# PCM1794.net
KiCad netlist of a schematic drawn in EAGLE
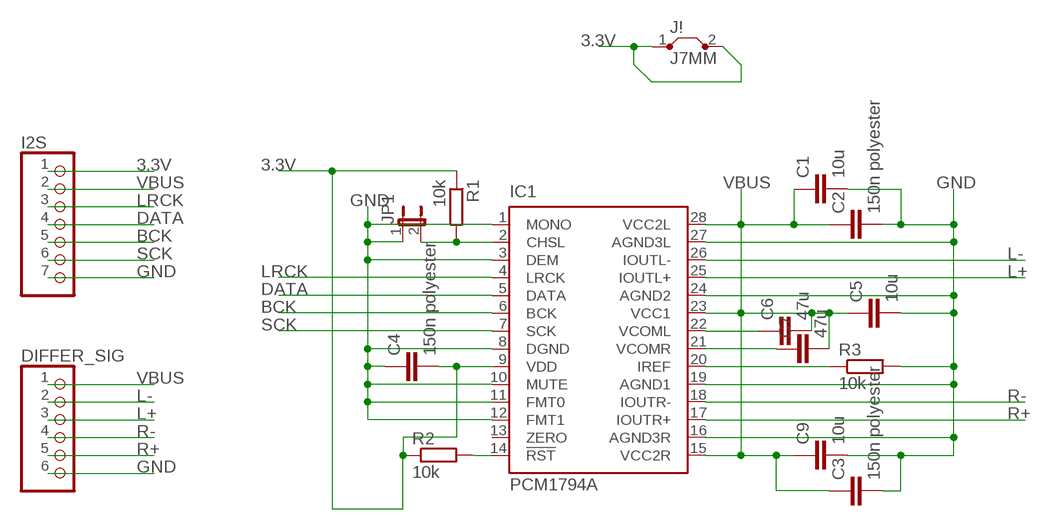
[diagram p0: schematic, sheet 1]

(export (version "E")
  (design (tool "Eeschema 10.0.6"))
  (components
    (comp (ref "C1")
      (value "10u")
      (footprint "eagle-import:C025-050X050")
      (libsource (lib "eagle-import") (part "C-EU025-050X050"))
    )
    (comp (ref "C2")
      (value "150n polyester")
      (footprint "eagle-import:C7.5B4")
      (libsource (lib "eagle-import") (part "C7.5/4"))
    )
    (comp (ref "C3")
      (value "150n polyester")
      (footprint "eagle-import:C7.5B4")
      (libsource (lib "eagle-import") (part "C7.5/4"))
    )
    (comp (ref "C4")
      (value "150n polyester")
      (footprint "eagle-import:C7.5B4")
      (libsource (lib "eagle-import") (part "C7.5/4"))
    )
    (comp (ref "C5")
      (value "10u")
      (footprint "eagle-import:C025-050X050")
      (libsource (lib "eagle-import") (part "C-EU025-050X050"))
    )
    (comp (ref "C6")
      (value "47u")
      (footprint "eagle-import:C025-050X050")
      (libsource (lib "eagle-import") (part "C-EU025-050X050"))
    )
    (comp (ref "C7")
      (value "47u")
      (footprint "eagle-import:C025-050X050")
      (libsource (lib "eagle-import") (part "C-EU025-050X050"))
    )
    (comp (ref "C9")
      (value "10u")
      (footprint "eagle-import:C025-050X050")
      (libsource (lib "eagle-import") (part "C-EU025-050X050"))
    )
    (comp (ref "DIFFER_SIG")
      (value "PINHD-1X6/90")
      (footprint "eagle-import:1X06_90")
      (libsource (lib "eagle-import") (part "PINHD-1X6/90"))
    )
    (comp (ref "I2S")
      (value "PINHD-1X7")
      (footprint "eagle-import:1X07")
      (libsource (lib "eagle-import") (part "PINHD-1X7"))
    )
    (comp (ref "IC1")
      (value "PCM1794A")
      (footprint "eagle-import:DB_R-PDSO-G28")
      (fields (field (name "MF") "TEXAS INSTRUMENTS") (field (name "MPN") "PCM1792DB"))
      (libsource (lib "eagle-import") (part "PCM1794A"))
    )
    (comp (ref "J!")
      (value "J7MM")
      (footprint "eagle-import:07")
      (libsource (lib "eagle-import") (part "J7MM"))
    )
    (comp (ref "JP1")
      (value "JP1E")
      (footprint "eagle-import:JP1")
      (libsource (lib "eagle-import") (part "JP1E"))
    )
    (comp (ref "R1")
      (value "10k")
      (footprint "eagle-import:0207_7")
      (libsource (lib "eagle-import") (part "R-EU_0207/7"))
    )
    (comp (ref "R2")
      (value "10k")
      (footprint "eagle-import:0207_7")
      (libsource (lib "eagle-import") (part "R-EU_0207/7"))
    )
    (comp (ref "R3")
      (value "10k")
      (footprint "eagle-import:0207_7")
      (libsource (lib "eagle-import") (part "R-EU_0207/7"))
    )
  )
  (nets
    (net (code "1") (name "/3.3V") (class "Default")
      (node (ref "C4") (pin "2") (pinfunction "2_2") (pintype "passive"))
      (node (ref "I2S") (pin "1") (pinfunction "1_1") (pintype "passive"))
      (node (ref "IC1") (pin "9") (pinfunction "VDD_9") (pintype "input"))
      (node (ref "J!") (pin "1") (pinfunction "1_1") (pintype "passive"))
      (node (ref "J!") (pin "2") (pinfunction "2_2") (pintype "passive"))
      (node (ref "R1") (pin "1") (pinfunction "1_1") (pintype "passive"))
      (node (ref "R2") (pin "1") (pinfunction "1_1") (pintype "passive"))
    )
    (net (code "2") (name "/BCK") (class "Default")
      (node (ref "I2S") (pin "5") (pinfunction "5_5") (pintype "passive"))
      (node (ref "IC1") (pin "6") (pinfunction "BCK_6") (pintype "input"))
    )
    (net (code "3") (name "/DATA") (class "Default")
      (node (ref "I2S") (pin "4") (pinfunction "4_4") (pintype "passive"))
      (node (ref "IC1") (pin "5") (pinfunction "DATA_5") (pintype "input"))
    )
    (net (code "4") (name "/GND") (class "Default")
      (node (ref "C1") (pin "2") (pinfunction "2_2") (pintype "passive"))
      (node (ref "C2") (pin "2") (pinfunction "2_2") (pintype "passive"))
      (node (ref "C3") (pin "2") (pinfunction "2_2") (pintype "passive"))
      (node (ref "C4") (pin "1") (pinfunction "1_1") (pintype "passive"))
      (node (ref "C5") (pin "2") (pinfunction "2_2") (pintype "passive"))
      (node (ref "C9") (pin "2") (pinfunction "2_2") (pintype "passive"))
      (node (ref "DIFFER_SIG") (pin "6") (pinfunction "6_6") (pintype "passive"))
      (node (ref "I2S") (pin "7") (pinfunction "7_7") (pintype "passive"))
      (node (ref "IC1") (pin "1") (pinfunction "MONO_1") (pintype "bidirectional"))
      (node (ref "IC1") (pin "10") (pinfunction "MUTE_10") (pintype "bidirectional"))
      (node (ref "IC1") (pin "11") (pinfunction "FMT0_11") (pintype "input"))
      (node (ref "IC1") (pin "12") (pinfunction "FMT1_12") (pintype "input"))
      (node (ref "IC1") (pin "16") (pinfunction "AGND3R_16") (pintype "input"))
      (node (ref "IC1") (pin "19") (pinfunction "AGND1_19") (pintype "input"))
      (node (ref "IC1") (pin "24") (pinfunction "AGND2_24") (pintype "input"))
      (node (ref "IC1") (pin "27") (pinfunction "AGND3L_27") (pintype "input"))
      (node (ref "IC1") (pin "3") (pinfunction "DEM_3") (pintype "input"))
      (node (ref "IC1") (pin "8") (pinfunction "DGND_8") (pintype "input"))
      (node (ref "JP1") (pin "1") (pinfunction "1_1") (pintype "passive"))
      (node (ref "R3") (pin "2") (pinfunction "2_2") (pintype "passive"))
    )
    (net (code "5") (name "/L+") (class "Default")
      (node (ref "DIFFER_SIG") (pin "3") (pinfunction "3_3") (pintype "passive"))
      (node (ref "IC1") (pin "25") (pinfunction "IOUTL+_25") (pintype "output"))
    )
    (net (code "6") (name "/L-") (class "Default")
      (node (ref "DIFFER_SIG") (pin "2") (pinfunction "2_2") (pintype "passive"))
      (node (ref "IC1") (pin "26") (pinfunction "IOUTL-_26") (pintype "output"))
    )
    (net (code "7") (name "/LRCK") (class "Default")
      (node (ref "I2S") (pin "3") (pinfunction "3_3") (pintype "passive"))
      (node (ref "IC1") (pin "4") (pinfunction "LRCK_4") (pintype "input"))
    )
    (net (code "8") (name "/R+") (class "Default")
      (node (ref "DIFFER_SIG") (pin "5") (pinfunction "5_5") (pintype "passive"))
      (node (ref "IC1") (pin "17") (pinfunction "IOUTR+_17") (pintype "output"))
    )
    (net (code "9") (name "/R-") (class "Default")
      (node (ref "DIFFER_SIG") (pin "4") (pinfunction "4_4") (pintype "passive"))
      (node (ref "IC1") (pin "18") (pinfunction "IOUTR-_18") (pintype "output"))
    )
    (net (code "10") (name "/SCK") (class "Default")
      (node (ref "I2S") (pin "6") (pinfunction "6_6") (pintype "passive"))
      (node (ref "IC1") (pin "7") (pinfunction "SCK_7") (pintype "input"))
    )
    (net (code "11") (name "/VBUS") (class "Default")
      (node (ref "C1") (pin "1") (pinfunction "1_1") (pintype "passive"))
      (node (ref "C2") (pin "1") (pinfunction "1_1") (pintype "passive"))
      (node (ref "C3") (pin "1") (pinfunction "1_1") (pintype "passive"))
      (node (ref "C5") (pin "1") (pinfunction "1_1") (pintype "passive"))
      (node (ref "C6") (pin "2") (pinfunction "2_2") (pintype "passive"))
      (node (ref "C7") (pin "2") (pinfunction "2_2") (pintype "passive"))
      (node (ref "C9") (pin "1") (pinfunction "1_1") (pintype "passive"))
      (node (ref "DIFFER_SIG") (pin "1") (pinfunction "1_1") (pintype "passive"))
      (node (ref "I2S") (pin "2") (pinfunction "2_2") (pintype "passive"))
      (node (ref "IC1") (pin "15") (pinfunction "VCC2R_15") (pintype "input"))
      (node (ref "IC1") (pin "23") (pinfunction "VCC1_23") (pintype "input"))
      (node (ref "IC1") (pin "28") (pinfunction "VCC2L_28") (pintype "input"))
    )
    (net (code "12") (name "Net-(IC1-CHSL)") (class "Default")
      (node (ref "IC1") (pin "2") (pinfunction "CHSL_2") (pintype "bidirectional"))
      (node (ref "JP1") (pin "2") (pinfunction "2_2") (pintype "passive"))
      (node (ref "R1") (pin "2") (pinfunction "2_2") (pintype "passive"))
    )
    (net (code "13") (name "Net-(IC1-IREF)") (class "Default")
      (node (ref "IC1") (pin "20") (pinfunction "IREF_20") (pintype "output"))
      (node (ref "R3") (pin "1") (pinfunction "1_1") (pintype "passive"))
    )
    (net (code "14") (name "Net-(IC1-VCOML)") (class "Default")
      (node (ref "C6") (pin "1") (pinfunction "1_1") (pintype "passive"))
      (node (ref "IC1") (pin "22") (pinfunction "VCOML_22") (pintype "input"))
    )
    (net (code "15") (name "Net-(IC1-VCOMR)") (class "Default")
      (node (ref "C7") (pin "1") (pinfunction "1_1") (pintype "passive"))
      (node (ref "IC1") (pin "21") (pinfunction "VCOMR_21") (pintype "input"))
    )
    (net (code "16") (name "Net-(IC1-~{RST})") (class "Default")
      (node (ref "IC1") (pin "14") (pinfunction "~{RST}_14") (pintype "input"))
      (node (ref "R2") (pin "2") (pinfunction "2_2") (pintype "passive"))
    )
    (net (code "17") (name "unconnected-(IC1-ZERO-Pad13)") (class "Default")
      (node (ref "IC1") (pin "13") (pinfunction "ZERO_13") (pintype "bidirectional"))
    )
  )
)
